# 06_SAMA7G54-DDR3.net
KiCad netlist of a schematic drawn in Altium Designer
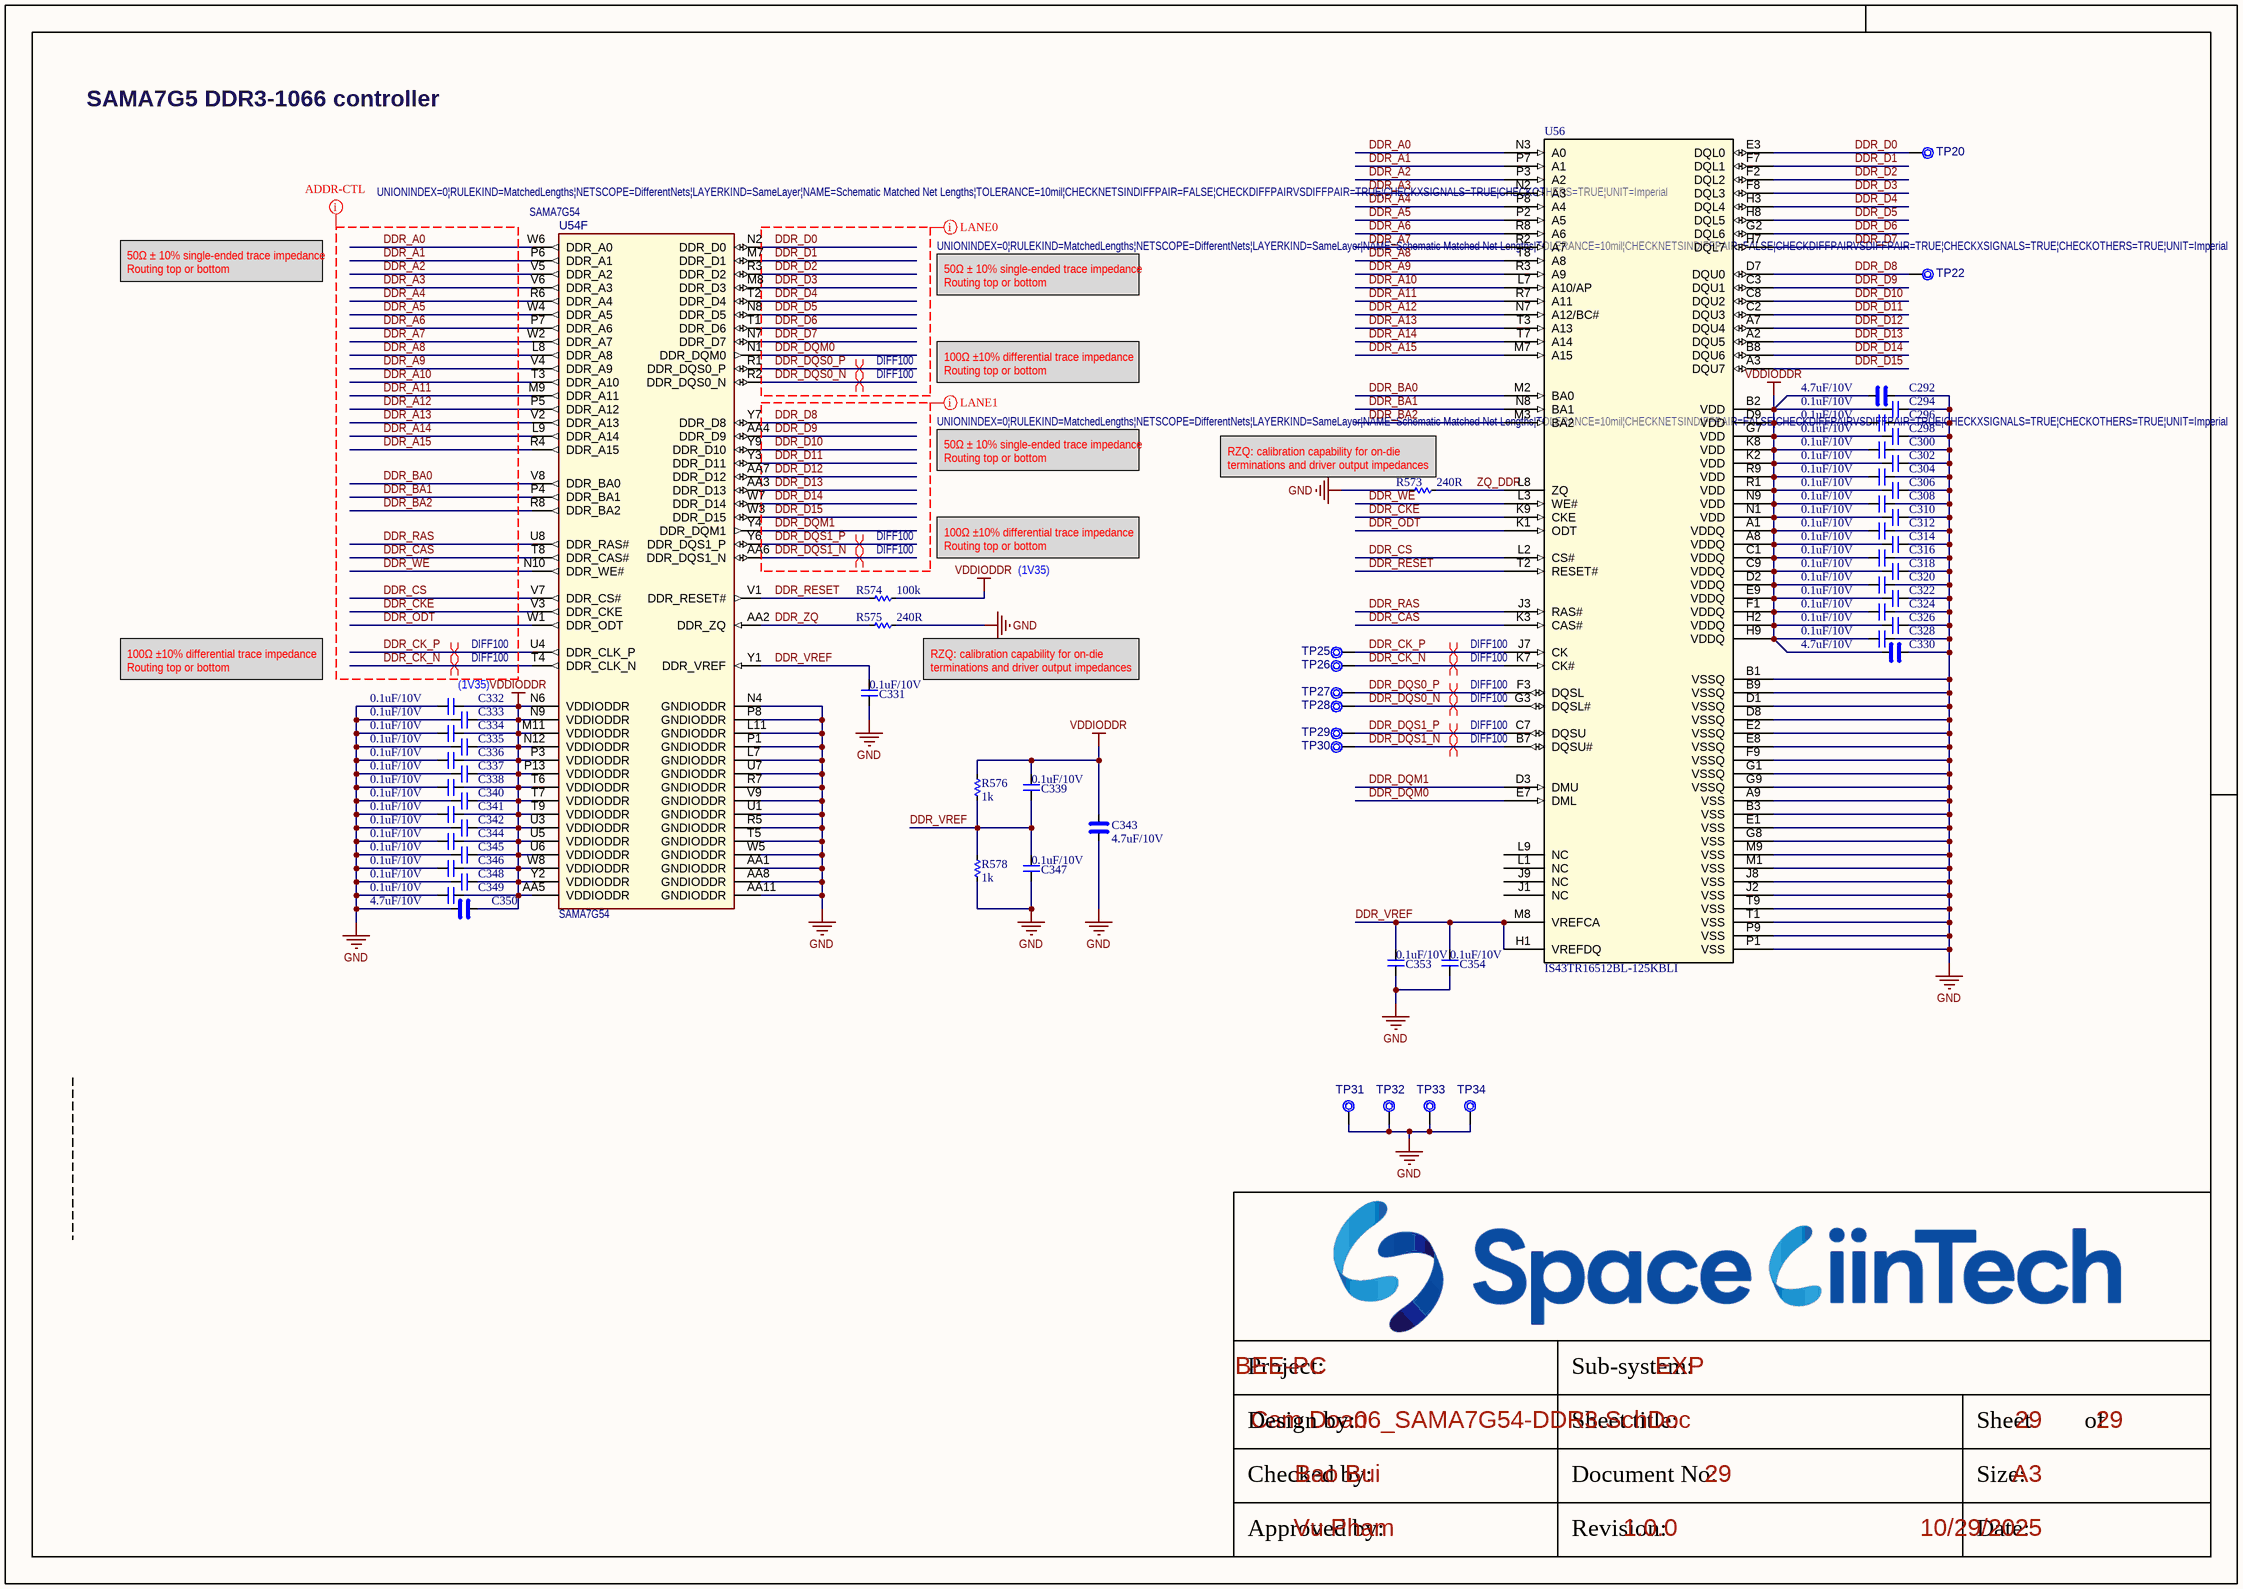
[diagram p0: 06_SAMA7G54-DDR3.SchDoc]

(export (version "E")
  (design (tool "Eeschema 10.0.6"))
  (components
    (comp (ref "C292")
      (value "4.7uF/10V")
      (footprint "CAP_C_1005X50_L")
      (description "CAP CHIP High Value")
      (libsource (lib "LABLIB") (part "_CAP_C_High_2"))
    )
    (comp (ref "C294")
      (value "0.1uF/10V")
      (footprint "CAP_C_0603x30")
      (description "CAP CHIP")
      (libsource (lib "LABLIB") (part "_CAP_C_2"))
    )
    (comp (ref "C296")
      (value "0.1uF/10V")
      (footprint "CAP_C_0603x30")
      (description "CAP CHIP")
      (libsource (lib "LABLIB") (part "_CAP_C_2"))
    )
    (comp (ref "C298")
      (value "0.1uF/10V")
      (footprint "CAP_C_0603x30")
      (description "CAP CHIP")
      (libsource (lib "LABLIB") (part "_CAP_C_2"))
    )
    (comp (ref "C300")
      (value "0.1uF/10V")
      (footprint "CAP_C_0603x30")
      (description "CAP CHIP")
      (libsource (lib "LABLIB") (part "_CAP_C_2"))
    )
    (comp (ref "C302")
      (value "0.1uF/10V")
      (footprint "CAP_C_0603x30")
      (description "CAP CHIP")
      (libsource (lib "LABLIB") (part "_CAP_C_2"))
    )
    (comp (ref "C304")
      (value "0.1uF/10V")
      (footprint "CAP_C_0603x30")
      (description "CAP CHIP")
      (libsource (lib "LABLIB") (part "_CAP_C_2"))
    )
    (comp (ref "C306")
      (value "0.1uF/10V")
      (footprint "CAP_C_0603x30")
      (description "CAP CHIP")
      (libsource (lib "LABLIB") (part "_CAP_C_2"))
    )
    (comp (ref "C308")
      (value "0.1uF/10V")
      (footprint "CAP_C_0603x30")
      (description "CAP CHIP")
      (libsource (lib "LABLIB") (part "_CAP_C_2"))
    )
    (comp (ref "C310")
      (value "0.1uF/10V")
      (footprint "CAP_C_0603x30")
      (description "CAP CHIP")
      (libsource (lib "LABLIB") (part "_CAP_C_2"))
    )
    (comp (ref "C312")
      (value "0.1uF/10V")
      (footprint "CAP_C_0603x30")
      (description "CAP CHIP")
      (libsource (lib "LABLIB") (part "_CAP_C_2"))
    )
    (comp (ref "C314")
      (value "0.1uF/10V")
      (footprint "CAP_C_0603x30")
      (description "CAP CHIP")
      (libsource (lib "LABLIB") (part "_CAP_C_2"))
    )
    (comp (ref "C316")
      (value "0.1uF/10V")
      (footprint "CAP_C_0603x30")
      (description "CAP CHIP")
      (libsource (lib "LABLIB") (part "_CAP_C_2"))
    )
    (comp (ref "C318")
      (value "0.1uF/10V")
      (footprint "CAP_C_0603x30")
      (description "CAP CHIP")
      (libsource (lib "LABLIB") (part "_CAP_C_2"))
    )
    (comp (ref "C320")
      (value "0.1uF/10V")
      (footprint "CAP_C_0603x30")
      (description "CAP CHIP")
      (libsource (lib "LABLIB") (part "_CAP_C_2"))
    )
    (comp (ref "C322")
      (value "0.1uF/10V")
      (footprint "CAP_C_0603x30")
      (description "CAP CHIP")
      (libsource (lib "LABLIB") (part "_CAP_C_2"))
    )
    (comp (ref "C324")
      (value "0.1uF/10V")
      (footprint "CAP_C_0603x30")
      (description "CAP CHIP")
      (libsource (lib "LABLIB") (part "_CAP_C_2"))
    )
    (comp (ref "C326")
      (value "0.1uF/10V")
      (footprint "CAP_C_0603x30")
      (description "CAP CHIP")
      (libsource (lib "LABLIB") (part "_CAP_C_2"))
    )
    (comp (ref "C328")
      (value "0.1uF/10V")
      (footprint "CAP_C_0603x30")
      (description "CAP CHIP")
      (libsource (lib "LABLIB") (part "_CAP_C_2"))
    )
    (comp (ref "C330")
      (value "4.7uF/10V")
      (footprint "CAP_C_1005X50_L")
      (description "CAP CHIP High Value")
      (libsource (lib "LABLIB") (part "_CAP_C_High_2"))
    )
    (comp (ref "C331")
      (value "0.1uF/10V")
      (footprint "CAP_C_0603x30")
      (description "CAP CHIP")
      (libsource (lib "LABLIB") (part "_CAP_C_2"))
    )
    (comp (ref "C332")
      (value "0.1uF/10V")
      (footprint "CAP_C_0603x30")
      (description "CAP CHIP")
      (libsource (lib "LABLIB") (part "_CAP_C_2"))
    )
    (comp (ref "C333")
      (value "0.1uF/10V")
      (footprint "CAP_C_0603x30")
      (description "CAP CHIP")
      (libsource (lib "LABLIB") (part "_CAP_C_2"))
    )
    (comp (ref "C334")
      (value "0.1uF/10V")
      (footprint "CAP_C_0603x30")
      (description "CAP CHIP")
      (libsource (lib "LABLIB") (part "_CAP_C_2"))
    )
    (comp (ref "C335")
      (value "0.1uF/10V")
      (footprint "CAP_C_0603x30")
      (description "CAP CHIP")
      (libsource (lib "LABLIB") (part "_CAP_C_2"))
    )
    (comp (ref "C336")
      (value "0.1uF/10V")
      (footprint "CAP_C_0603x30")
      (description "CAP CHIP")
      (libsource (lib "LABLIB") (part "_CAP_C_2"))
    )
    (comp (ref "C337")
      (value "0.1uF/10V")
      (footprint "CAP_C_0603x30")
      (description "CAP CHIP")
      (libsource (lib "LABLIB") (part "_CAP_C_2"))
    )
    (comp (ref "C338")
      (value "0.1uF/10V")
      (footprint "CAP_C_0603x30")
      (description "CAP CHIP")
      (libsource (lib "LABLIB") (part "_CAP_C_2"))
    )
    (comp (ref "C339")
      (value "0.1uF/10V")
      (footprint "CAP_C_0603x30")
      (description "CAP CHIP")
      (libsource (lib "LABLIB") (part "_CAP_C_2"))
    )
    (comp (ref "C340")
      (value "0.1uF/10V")
      (footprint "CAP_C_0603x30")
      (description "CAP CHIP")
      (libsource (lib "LABLIB") (part "_CAP_C_2"))
    )
    (comp (ref "C341")
      (value "0.1uF/10V")
      (footprint "CAP_C_0603x30")
      (description "CAP CHIP")
      (libsource (lib "LABLIB") (part "_CAP_C_2"))
    )
    (comp (ref "C342")
      (value "0.1uF/10V")
      (footprint "CAP_C_0603x30")
      (description "CAP CHIP")
      (libsource (lib "LABLIB") (part "_CAP_C_2"))
    )
    (comp (ref "C343")
      (value "4.7uF/10V")
      (footprint "CAP_C_1005X60")
      (description "CAP CHIP High Value")
      (libsource (lib "LABLIB") (part "_CAP_C_High_2"))
    )
    (comp (ref "C344")
      (value "0.1uF/10V")
      (footprint "CAP_C_0603x30")
      (description "CAP CHIP")
      (libsource (lib "LABLIB") (part "_CAP_C_2"))
    )
    (comp (ref "C345")
      (value "0.1uF/10V")
      (footprint "CAP_C_0603x30")
      (description "CAP CHIP")
      (libsource (lib "LABLIB") (part "_CAP_C_2"))
    )
    (comp (ref "C346")
      (value "0.1uF/10V")
      (footprint "CAP_C_0603x30")
      (description "CAP CHIP")
      (libsource (lib "LABLIB") (part "_CAP_C_2"))
    )
    (comp (ref "C347")
      (value "0.1uF/10V")
      (footprint "CAP_C_0603x30")
      (description "CAP CHIP")
      (libsource (lib "LABLIB") (part "_CAP_C_2"))
    )
    (comp (ref "C348")
      (value "0.1uF/10V")
      (footprint "CAP_C_0603x30")
      (description "CAP CHIP")
      (libsource (lib "LABLIB") (part "_CAP_C_2"))
    )
    (comp (ref "C349")
      (value "0.1uF/10V")
      (footprint "CAP_C_0603x30")
      (description "CAP CHIP")
      (libsource (lib "LABLIB") (part "_CAP_C_2"))
    )
    (comp (ref "C350")
      (value "4.7uF/10V")
      (footprint "CAP_C_1005X50_L")
      (description "CAP CHIP High Value")
      (libsource (lib "LABLIB") (part "_CAP_C_High_2"))
    )
    (comp (ref "C353")
      (value "0.1uF/10V")
      (footprint "CAP_C_0603x30")
      (description "CAP CHIP")
      (libsource (lib "LABLIB") (part "_CAP_C_2"))
    )
    (comp (ref "C354")
      (value "0.1uF/10V")
      (footprint "CAP_C_0603x30")
      (description "CAP CHIP")
      (libsource (lib "LABLIB") (part "_CAP_C_2"))
    )
    (comp (ref "R573")
      (value "240R")
      (footprint "RES_C_0603X30")
      (description "RES")
      (libsource (lib "LABLIB") (part "_RES_B_2"))
    )
    (comp (ref "R574")
      (value "100k")
      (footprint "RES_C_0603X30")
      (description "RES")
      (libsource (lib "LABLIB") (part "_RES_B_2"))
    )
    (comp (ref "R575")
      (value "240R")
      (footprint "RES_C_0603X30")
      (description "RES")
      (libsource (lib "LABLIB") (part "_RES_B_2"))
    )
    (comp (ref "R576")
      (value "1k")
      (footprint "RES_C_0603X30")
      (description "RES")
      (libsource (lib "LABLIB") (part "_RES_B_2"))
    )
    (comp (ref "R578")
      (value "1k")
      (footprint "RES_C_0603X30")
      (description "RES")
      (libsource (lib "LABLIB") (part "_RES_B_2"))
    )
    (comp (ref "TP20")
      (value "Test Point No BOM")
      (footprint "Testpoint_80")
      (description "Test Point")
      (fields (field (name "OWNER") "Cristian Papuc"))
      (libsource (lib "MCHP-CDB") (part "Test Point No BOM"))
    )
    (comp (ref "TP22")
      (value "Test Point No BOM")
      (footprint "Testpoint_80")
      (description "Test Point")
      (fields (field (name "OWNER") "Cristian Papuc"))
      (libsource (lib "MCHP-CDB") (part "Test Point No BOM"))
    )
    (comp (ref "TP25")
      (value "Test Point No BOM")
      (footprint "Testpoint_80")
      (description "Test Point")
      (fields (field (name "OWNER") "Cristian Papuc"))
      (libsource (lib "MCHP-CDB") (part "Test Point No BOM"))
    )
    (comp (ref "TP26")
      (value "Test Point No BOM")
      (footprint "Testpoint_80")
      (description "Test Point")
      (fields (field (name "OWNER") "Cristian Papuc"))
      (libsource (lib "MCHP-CDB") (part "Test Point No BOM"))
    )
    (comp (ref "TP27")
      (value "Test Point No BOM")
      (footprint "Testpoint_80")
      (description "Test Point")
      (fields (field (name "OWNER") "Cristian Papuc"))
      (libsource (lib "MCHP-CDB") (part "Test Point No BOM"))
    )
    (comp (ref "TP28")
      (value "Test Point No BOM")
      (footprint "Testpoint_80")
      (description "Test Point")
      (fields (field (name "OWNER") "Cristian Papuc"))
      (libsource (lib "MCHP-CDB") (part "Test Point No BOM"))
    )
    (comp (ref "TP29")
      (value "Test Point No BOM")
      (footprint "Testpoint_80")
      (description "Test Point")
      (fields (field (name "OWNER") "Cristian Papuc"))
      (libsource (lib "MCHP-CDB") (part "Test Point No BOM"))
    )
    (comp (ref "TP30")
      (value "Test Point No BOM")
      (footprint "Testpoint_80")
      (description "Test Point")
      (fields (field (name "OWNER") "Cristian Papuc"))
      (libsource (lib "MCHP-CDB") (part "Test Point No BOM"))
    )
    (comp (ref "TP31")
      (value "Test Point No BOM")
      (footprint "Testpoint_80")
      (description "Test Point")
      (fields (field (name "OWNER") "Cristian Papuc"))
      (libsource (lib "MCHP-CDB") (part "Test Point No BOM"))
    )
    (comp (ref "TP32")
      (value "Test Point No BOM")
      (footprint "Testpoint_80")
      (description "Test Point")
      (fields (field (name "OWNER") "Cristian Papuc"))
      (libsource (lib "MCHP-CDB") (part "Test Point No BOM"))
    )
    (comp (ref "TP33")
      (value "Test Point No BOM")
      (footprint "Testpoint_80")
      (description "Test Point")
      (fields (field (name "OWNER") "Cristian Papuc"))
      (libsource (lib "MCHP-CDB") (part "Test Point No BOM"))
    )
    (comp (ref "TP34")
      (value "Test Point No BOM")
      (footprint "Testpoint_80")
      (description "Test Point")
      (fields (field (name "OWNER") "Cristian Papuc"))
      (libsource (lib "MCHP-CDB") (part "Test Point No BOM"))
    )
    (comp (ref "U54")
      (value "SAMA7G54")
      (footprint "TFBGA-343_14x14")
      (description "SAMA7G54 MPU 1000MHz Cortex-A7 TFBGA-343")
      (fields (field (name "ALTIUM_VALUE") "SAMA7G54") (field (name "OWNER") "Ciprian Abramov"))
      (libsource (lib "MCHP-CDB") (part "SAMA7G54 TFBGA-343"))
    )
    (comp (ref "U56")
      (value "IS43TR16512BL-125KBLI")
      (footprint "TWBGA96_ISI")
      (description "DDR3L")
      (fields (field (name "COPYRIGHT") "Copyright (C) 2025 Ultra Librarian. All rights reserved."))
      (libsource (lib "LABLIB") (part "IC_RAM_IS43TR16512BL-125KBLI"))
    )
  )
  (nets
    (net (code "1") (name "/DDR_A0") (class "Default")
      (node (ref "U54") (pin "W6") (pinfunction "DDR_A0_W6") (pintype "output"))
      (node (ref "U56") (pin "N3") (pinfunction "A0_N3") (pintype "input"))
    )
    (net (code "2") (name "/DDR_A1") (class "Default")
      (node (ref "U54") (pin "P6") (pinfunction "DDR_A1_P6") (pintype "output"))
      (node (ref "U56") (pin "P7") (pinfunction "A1_P7") (pintype "input"))
    )
    (net (code "3") (name "/DDR_A2") (class "Default")
      (node (ref "U54") (pin "V5") (pinfunction "DDR_A2_V5") (pintype "output"))
      (node (ref "U56") (pin "P3") (pinfunction "A2_P3") (pintype "input"))
    )
    (net (code "4") (name "/DDR_A3") (class "Default")
      (node (ref "U54") (pin "V6") (pinfunction "DDR_A3_V6") (pintype "output"))
      (node (ref "U56") (pin "N2") (pinfunction "A3_N2") (pintype "input"))
    )
    (net (code "5") (name "/DDR_A4") (class "Default")
      (node (ref "U54") (pin "R6") (pinfunction "DDR_A4_R6") (pintype "output"))
      (node (ref "U56") (pin "P8") (pinfunction "A4_P8") (pintype "input"))
    )
    (net (code "6") (name "/DDR_A5") (class "Default")
      (node (ref "U54") (pin "W4") (pinfunction "DDR_A5_W4") (pintype "output"))
      (node (ref "U56") (pin "P2") (pinfunction "A5_P2") (pintype "input"))
    )
    (net (code "7") (name "/DDR_A6") (class "Default")
      (node (ref "U54") (pin "P7") (pinfunction "DDR_A6_P7") (pintype "output"))
      (node (ref "U56") (pin "R8") (pinfunction "A6_R8") (pintype "input"))
    )
    (net (code "8") (name "/DDR_A7") (class "Default")
      (node (ref "U54") (pin "W2") (pinfunction "DDR_A7_W2") (pintype "output"))
      (node (ref "U56") (pin "R2") (pinfunction "A7_R2") (pintype "input"))
    )
    (net (code "9") (name "/DDR_A8") (class "Default")
      (node (ref "U54") (pin "L8") (pinfunction "DDR_A8_L8") (pintype "output"))
      (node (ref "U56") (pin "T8") (pinfunction "A8_T8") (pintype "input"))
    )
    (net (code "10") (name "/DDR_A9") (class "Default")
      (node (ref "U54") (pin "V4") (pinfunction "DDR_A9_V4") (pintype "output"))
      (node (ref "U56") (pin "R3") (pinfunction "A9_R3") (pintype "input"))
    )
    (net (code "11") (name "/DDR_A10") (class "Default")
      (node (ref "U54") (pin "T3") (pinfunction "DDR_A10_T3") (pintype "output"))
      (node (ref "U56") (pin "L7") (pinfunction "A10/AP_L7") (pintype "input"))
    )
    (net (code "12") (name "/DDR_A11") (class "Default")
      (node (ref "U54") (pin "M9") (pinfunction "DDR_A11_M9") (pintype "output"))
      (node (ref "U56") (pin "R7") (pinfunction "A11_R7") (pintype "input"))
    )
    (net (code "13") (name "/DDR_A12") (class "Default")
      (node (ref "U54") (pin "P5") (pinfunction "DDR_A12_P5") (pintype "output"))
      (node (ref "U56") (pin "N7") (pinfunction "A12/BC#_N7") (pintype "input"))
    )
    (net (code "14") (name "/DDR_A13") (class "Default")
      (node (ref "U54") (pin "V2") (pinfunction "DDR_A13_V2") (pintype "output"))
      (node (ref "U56") (pin "T3") (pinfunction "A13_T3") (pintype "input"))
    )
    (net (code "15") (name "/DDR_A14") (class "Default")
      (node (ref "U54") (pin "L9") (pinfunction "DDR_A14_L9") (pintype "output"))
      (node (ref "U56") (pin "T7") (pinfunction "A14_T7") (pintype "input"))
    )
    (net (code "16") (name "/DDR_A15") (class "Default")
      (node (ref "U54") (pin "R4") (pinfunction "DDR_A15_R4") (pintype "output"))
      (node (ref "U56") (pin "M7") (pinfunction "A15_M7") (pintype "input"))
    )
    (net (code "17") (name "/DDR_BA0") (class "Default")
      (node (ref "U54") (pin "V8") (pinfunction "DDR_BA0_V8") (pintype "output"))
      (node (ref "U56") (pin "M2") (pinfunction "BA0_M2") (pintype "input"))
    )
    (net (code "18") (name "/DDR_BA1") (class "Default")
      (node (ref "U54") (pin "P4") (pinfunction "DDR_BA1_P4") (pintype "output"))
      (node (ref "U56") (pin "N8") (pinfunction "BA1_N8") (pintype "input"))
    )
    (net (code "19") (name "/DDR_BA2") (class "Default")
      (node (ref "U54") (pin "R8") (pinfunction "DDR_BA2_R8") (pintype "output"))
      (node (ref "U56") (pin "M3") (pinfunction "BA2_M3") (pintype "input"))
    )
    (net (code "20") (name "/DDR_CAS") (class "Default")
      (node (ref "U54") (pin "T8") (pinfunction "DDR_CAS#_T8") (pintype "output"))
      (node (ref "U56") (pin "K3") (pinfunction "CAS#_K3") (pintype "input"))
    )
    (net (code "21") (name "/DDR_CKE") (class "Default")
      (node (ref "U54") (pin "V3") (pinfunction "DDR_CKE_V3") (pintype "output"))
      (node (ref "U56") (pin "K9") (pinfunction "CKE_K9") (pintype "input"))
    )
    (net (code "22") (name "/DDR_CK_N") (class "Default")
      (node (ref "TP26") (pin "1") (pinfunction "1_1") (pintype "passive"))
      (node (ref "U54") (pin "T4") (pinfunction "DDR_CLK_N_T4") (pintype "output"))
      (node (ref "U56") (pin "K7") (pinfunction "CK#_K7") (pintype "input"))
    )
    (net (code "23") (name "/DDR_CK_P") (class "Default")
      (node (ref "TP25") (pin "1") (pinfunction "1_1") (pintype "passive"))
      (node (ref "U54") (pin "U4") (pinfunction "DDR_CLK_P_U4") (pintype "output"))
      (node (ref "U56") (pin "J7") (pinfunction "CK_J7") (pintype "input"))
    )
    (net (code "24") (name "/DDR_CS") (class "Default")
      (node (ref "U54") (pin "V7") (pinfunction "DDR_CS#_V7") (pintype "output"))
      (node (ref "U56") (pin "L2") (pinfunction "CS#_L2") (pintype "input"))
    )
    (net (code "25") (name "/DDR_D0") (class "Default")
      (node (ref "TP20") (pin "1") (pinfunction "1_1") (pintype "passive"))
      (node (ref "U54") (pin "N2") (pinfunction "DDR_D0_N2") (pintype "bidirectional"))
      (node (ref "U56") (pin "E3") (pinfunction "DQL0_E3") (pintype "bidirectional"))
    )
    (net (code "26") (name "/DDR_D1") (class "Default")
      (node (ref "U54") (pin "M7") (pinfunction "DDR_D1_M7") (pintype "bidirectional"))
      (node (ref "U56") (pin "F7") (pinfunction "DQL1_F7") (pintype "bidirectional"))
    )
    (net (code "27") (name "/DDR_D2") (class "Default")
      (node (ref "U54") (pin "R3") (pinfunction "DDR_D2_R3") (pintype "bidirectional"))
      (node (ref "U56") (pin "F2") (pinfunction "DQL2_F2") (pintype "bidirectional"))
    )
    (net (code "28") (name "/DDR_D3") (class "Default")
      (node (ref "U54") (pin "M8") (pinfunction "DDR_D3_M8") (pintype "bidirectional"))
      (node (ref "U56") (pin "F8") (pinfunction "DQL3_F8") (pintype "bidirectional"))
    )
    (net (code "29") (name "/DDR_D4") (class "Default")
      (node (ref "U54") (pin "T2") (pinfunction "DDR_D4_T2") (pintype "bidirectional"))
      (node (ref "U56") (pin "H3") (pinfunction "DQL4_H3") (pintype "bidirectional"))
    )
    (net (code "30") (name "/DDR_D5") (class "Default")
      (node (ref "U54") (pin "N8") (pinfunction "DDR_D5_N8") (pintype "bidirectional"))
      (node (ref "U56") (pin "H8") (pinfunction "DQL5_H8") (pintype "bidirectional"))
    )
    (net (code "31") (name "/DDR_D6") (class "Default")
      (node (ref "U54") (pin "T1") (pinfunction "DDR_D6_T1") (pintype "bidirectional"))
      (node (ref "U56") (pin "G2") (pinfunction "DQL6_G2") (pintype "bidirectional"))
    )
    (net (code "32") (name "/DDR_D7") (class "Default")
      (node (ref "U54") (pin "N7") (pinfunction "DDR_D7_N7") (pintype "bidirectional"))
      (node (ref "U56") (pin "H7") (pinfunction "DQL7_H7") (pintype "bidirectional"))
    )
    (net (code "33") (name "/DDR_D8") (class "Default")
      (node (ref "TP22") (pin "1") (pinfunction "1_1") (pintype "passive"))
      (node (ref "U54") (pin "Y7") (pinfunction "DDR_D8_Y7") (pintype "bidirectional"))
      (node (ref "U56") (pin "D7") (pinfunction "DQU0_D7") (pintype "bidirectional"))
    )
    (net (code "34") (name "/DDR_D9") (class "Default")
      (node (ref "U54") (pin "AA4") (pinfunction "DDR_D9_AA4") (pintype "bidirectional"))
      (node (ref "U56") (pin "C3") (pinfunction "DQU1_C3") (pintype "bidirectional"))
    )
    (net (code "35") (name "/DDR_D10") (class "Default")
      (node (ref "U54") (pin "Y9") (pinfunction "DDR_D10_Y9") (pintype "bidirectional"))
      (node (ref "U56") (pin "C8") (pinfunction "DQU2_C8") (pintype "bidirectional"))
    )
    (net (code "36") (name "/DDR_D11") (class "Default")
      (node (ref "U54") (pin "Y3") (pinfunction "DDR_D11_Y3") (pintype "bidirectional"))
      (node (ref "U56") (pin "C2") (pinfunction "DQU3_C2") (pintype "bidirectional"))
    )
    (net (code "37") (name "/DDR_D12") (class "Default")
      (node (ref "U54") (pin "AA7") (pinfunction "DDR_D12_AA7") (pintype "bidirectional"))
      (node (ref "U56") (pin "A7") (pinfunction "DQU4_A7") (pintype "bidirectional"))
    )
    (net (code "38") (name "/DDR_D13") (class "Default")
      (node (ref "U54") (pin "AA3") (pinfunction "DDR_D13_AA3") (pintype "bidirectional"))
      (node (ref "U56") (pin "A2") (pinfunction "DQU5_A2") (pintype "bidirectional"))
    )
    (net (code "39") (name "/DDR_D14") (class "Default")
      (node (ref "U54") (pin "W7") (pinfunction "DDR_D14_W7") (pintype "bidirectional"))
      (node (ref "U56") (pin "B8") (pinfunction "DQU6_B8") (pintype "bidirectional"))
    )
    (net (code "40") (name "/DDR_D15") (class "Default")
      (node (ref "U54") (pin "W3") (pinfunction "DDR_D15_W3") (pintype "bidirectional"))
      (node (ref "U56") (pin "A3") (pinfunction "DQU7_A3") (pintype "bidirectional"))
    )
    (net (code "41") (name "/DDR_DQM0") (class "Default")
      (node (ref "U54") (pin "N1") (pinfunction "DDR_DQM0_N1") (pintype "output"))
      (node (ref "U56") (pin "E7") (pinfunction "DML_E7") (pintype "input"))
    )
    (net (code "42") (name "/DDR_DQM1") (class "Default")
      (node (ref "U54") (pin "Y4") (pinfunction "DDR_DQM1_Y4") (pintype "output"))
      (node (ref "U56") (pin "D3") (pinfunction "DMU_D3") (pintype "input"))
    )
    (net (code "43") (name "/DDR_DQS0_N") (class "Default")
      (node (ref "TP28") (pin "1") (pinfunction "1_1") (pintype "passive"))
      (node (ref "U54") (pin "R2") (pinfunction "DDR_DQS0_N_R2") (pintype "bidirectional"))
      (node (ref "U56") (pin "G3") (pinfunction "DQSL#_G3") (pintype "bidirectional"))
    )
    (net (code "44") (name "/DDR_DQS0_P") (class "Default")
      (node (ref "TP27") (pin "1") (pinfunction "1_1") (pintype "passive"))
      (node (ref "U54") (pin "R1") (pinfunction "DDR_DQS0_P_R1") (pintype "bidirectional"))
      (node (ref "U56") (pin "F3") (pinfunction "DQSL_F3") (pintype "bidirectional"))
    )
    (net (code "45") (name "/DDR_DQS1_N") (class "Default")
      (node (ref "TP30") (pin "1") (pinfunction "1_1") (pintype "passive"))
      (node (ref "U54") (pin "AA6") (pinfunction "DDR_DQS1_N_AA6") (pintype "bidirectional"))
      (node (ref "U56") (pin "B7") (pinfunction "DQSU#_B7") (pintype "bidirectional"))
    )
    (net (code "46") (name "/DDR_DQS1_P") (class "Default")
      (node (ref "TP29") (pin "1") (pinfunction "1_1") (pintype "passive"))
      (node (ref "U54") (pin "Y6") (pinfunction "DDR_DQS1_P_Y6") (pintype "bidirectional"))
      (node (ref "U56") (pin "C7") (pinfunction "DQSU_C7") (pintype "bidirectional"))
    )
    (net (code "47") (name "/DDR_ODT") (class "Default")
      (node (ref "U54") (pin "W1") (pinfunction "DDR_ODT_W1") (pintype "output"))
      (node (ref "U56") (pin "K1") (pinfunction "ODT_K1") (pintype "input"))
    )
    (net (code "48") (name "/DDR_RAS") (class "Default")
      (node (ref "U54") (pin "U8") (pinfunction "DDR_RAS#_U8") (pintype "output"))
      (node (ref "U56") (pin "J3") (pinfunction "RAS#_J3") (pintype "input"))
    )
    (net (code "49") (name "/DDR_RESET") (class "Default")
      (node (ref "R574") (pin "2") (pinfunction "2_2") (pintype "passive"))
      (node (ref "U54") (pin "V1") (pinfunction "DDR_RESET#_V1") (pintype "output"))
      (node (ref "U56") (pin "T2") (pinfunction "RESET#_T2") (pintype "input"))
    )
    (net (code "50") (name "/DDR_VREF") (class "Default")
      (node (ref "C331") (pin "1") (pinfunction "1_1") (pintype "passive"))
      (node (ref "C339") (pin "2") (pinfunction "2_2") (pintype "passive"))
      (node (ref "C347") (pin "1") (pinfunction "1_1") (pintype "passive"))
      (node (ref "C353") (pin "1") (pinfunction "1_1") (pintype "passive"))
      (node (ref "C354") (pin "1") (pinfunction "1_1") (pintype "passive"))
      (node (ref "R576") (pin "2") (pinfunction "2_2") (pintype "passive"))
      (node (ref "R578") (pin "1") (pinfunction "1_1") (pintype "passive"))
      (node (ref "U54") (pin "Y1") (pinfunction "DDR_VREF_Y1") (pintype "input"))
      (node (ref "U56") (pin "H1") (pinfunction "VREFDQ_H1") (pintype "power_in"))
      (node (ref "U56") (pin "M8") (pinfunction "VREFCA_M8") (pintype "power_in"))
    )
    (net (code "51") (name "/DDR_WE") (class "Default")
      (node (ref "U54") (pin "N10") (pinfunction "DDR_WE#_N10") (pintype "output"))
      (node (ref "U56") (pin "L3") (pinfunction "WE#_L3") (pintype "input"))
    )
    (net (code "52") (name "/DDR_ZQ") (class "Default")
      (node (ref "R575") (pin "2") (pinfunction "2_2") (pintype "passive"))
      (node (ref "U54") (pin "AA2") (pinfunction "DDR_ZQ_AA2") (pintype "input"))
    )
    (net (code "53") (name "/ZQ_DDR") (class "Default")
      (node (ref "R573") (pin "1") (pinfunction "1_1") (pintype "passive"))
      (node (ref "U56") (pin "L8") (pinfunction "ZQ_L8") (pintype "power_in"))
    )
    (net (code "54") (name "GND") (class "Default")
      (node (ref "C292") (pin "1") (pinfunction "1_1") (pintype "passive"))
      (node (ref "C294") (pin "1") (pinfunction "1_1") (pintype "passive"))
      (node (ref "C296") (pin "1") (pinfunction "1_1") (pintype "passive"))
      (node (ref "C298") (pin "1") (pinfunction "1_1") (pintype "passive"))
      (node (ref "C300") (pin "1") (pinfunction "1_1") (pintype "passive"))
      (node (ref "C302") (pin "1") (pinfunction "1_1") (pintype "passive"))
      (node (ref "C304") (pin "1") (pinfunction "1_1") (pintype "passive"))
      (node (ref "C306") (pin "1") (pinfunction "1_1") (pintype "passive"))
      (node (ref "C308") (pin "1") (pinfunction "1_1") (pintype "passive"))
      (node (ref "C310") (pin "1") (pinfunction "1_1") (pintype "passive"))
      (node (ref "C312") (pin "1") (pinfunction "1_1") (pintype "passive"))
      (node (ref "C314") (pin "1") (pinfunction "1_1") (pintype "passive"))
      (node (ref "C316") (pin "1") (pinfunction "1_1") (pintype "passive"))
      (node (ref "C318") (pin "1") (pinfunction "1_1") (pintype "passive"))
      (node (ref "C320") (pin "1") (pinfunction "1_1") (pintype "passive"))
      (node (ref "C322") (pin "1") (pinfunction "1_1") (pintype "passive"))
      (node (ref "C324") (pin "1") (pinfunction "1_1") (pintype "passive"))
      (node (ref "C326") (pin "1") (pinfunction "1_1") (pintype "passive"))
      (node (ref "C328") (pin "1") (pinfunction "1_1") (pintype "passive"))
      (node (ref "C330") (pin "1") (pinfunction "1_1") (pintype "passive"))
      (node (ref "C331") (pin "2") (pinfunction "2_2") (pintype "passive"))
      (node (ref "C332") (pin "2") (pinfunction "2_2") (pintype "passive"))
      (node (ref "C333") (pin "2") (pinfunction "2_2") (pintype "passive"))
      (node (ref "C334") (pin "2") (pinfunction "2_2") (pintype "passive"))
      (node (ref "C335") (pin "2") (pinfunction "2_2") (pintype "passive"))
      (node (ref "C336") (pin "2") (pinfunction "2_2") (pintype "passive"))
      (node (ref "C337") (pin "2") (pinfunction "2_2") (pintype "passive"))
      (node (ref "C338") (pin "2") (pinfunction "2_2") (pintype "passive"))
      (node (ref "C340") (pin "2") (pinfunction "2_2") (pintype "passive"))
      (node (ref "C341") (pin "2") (pinfunction "2_2") (pintype "passive"))
      (node (ref "C342") (pin "2") (pinfunction "2_2") (pintype "passive"))
      (node (ref "C343") (pin "2") (pinfunction "2_2") (pintype "passive"))
      (node (ref "C344") (pin "2") (pinfunction "2_2") (pintype "passive"))
      (node (ref "C345") (pin "2") (pinfunction "2_2") (pintype "passive"))
      (node (ref "C346") (pin "2") (pinfunction "2_2") (pintype "passive"))
      (node (ref "C347") (pin "2") (pinfunction "2_2") (pintype "passive"))
      (node (ref "C348") (pin "2") (pinfunction "2_2") (pintype "passive"))
      (node (ref "C349") (pin "2") (pinfunction "2_2") (pintype "passive"))
      (node (ref "C350") (pin "2") (pinfunction "2_2") (pintype "passive"))
      (node (ref "C353") (pin "2") (pinfunction "2_2") (pintype "passive"))
      (node (ref "C354") (pin "2") (pinfunction "2_2") (pintype "passive"))
      (node (ref "R573") (pin "2") (pinfunction "2_2") (pintype "passive"))
      (node (ref "R575") (pin "1") (pinfunction "1_1") (pintype "passive"))
      (node (ref "R578") (pin "2") (pinfunction "2_2") (pintype "passive"))
      (node (ref "TP31") (pin "1") (pinfunction "1_1") (pintype "passive"))
      (node (ref "TP32") (pin "1") (pinfunction "1_1") (pintype "passive"))
      (node (ref "TP33") (pin "1") (pinfunction "1_1") (pintype "passive"))
      (node (ref "TP34") (pin "1") (pinfunction "1_1") (pintype "passive"))
      (node (ref "U54") (pin "AA1") (pinfunction "GNDIODDR_AA1") (pintype "power_in"))
      (node (ref "U54") (pin "AA11") (pinfunction "GNDIODDR_AA11") (pintype "power_in"))
      (node (ref "U54") (pin "AA8") (pinfunction "GNDIODDR_AA8") (pintype "power_in"))
      (node (ref "U54") (pin "L11") (pinfunction "GNDIODDR_L11") (pintype "power_in"))
      (node (ref "U54") (pin "L7") (pinfunction "GNDIODDR_L7") (pintype "power_in"))
      (node (ref "U54") (pin "N4") (pinfunction "GNDIODDR_N4") (pintype "power_in"))
      (node (ref "U54") (pin "P1") (pinfunction "GNDIODDR_P1") (pintype "power_in"))
      (node (ref "U54") (pin "P8") (pinfunction "GNDIODDR_P8") (pintype "power_in"))
      (node (ref "U54") (pin "R5") (pinfunction "GNDIODDR_R5") (pintype "power_in"))
      (node (ref "U54") (pin "R7") (pinfunction "GNDIODDR_R7") (pintype "power_in"))
      (node (ref "U54") (pin "T5") (pinfunction "GNDIODDR_T5") (pintype "power_in"))
      (node (ref "U54") (pin "U1") (pinfunction "GNDIODDR_U1") (pintype "power_in"))
      (node (ref "U54") (pin "U7") (pinfunction "GNDIODDR_U7") (pintype "power_in"))
      (node (ref "U54") (pin "V9") (pinfunction "GNDIODDR_V9") (pintype "power_in"))
      (node (ref "U54") (pin "W5") (pinfunction "GNDIODDR_W5") (pintype "power_in"))
      (node (ref "U56") (pin "A9") (pinfunction "VSS_A9") (pintype "power_in"))
      (node (ref "U56") (pin "B1") (pinfunction "VSSQ_B1") (pintype "power_in"))
      (node (ref "U56") (pin "B3") (pinfunction "VSS_B3") (pintype "power_in"))
      (node (ref "U56") (pin "B9") (pinfunction "VSSQ_B9") (pintype "power_in"))
      (node (ref "U56") (pin "D1") (pinfunction "VSSQ_D1") (pintype "power_in"))
      (node (ref "U56") (pin "D8") (pinfunction "VSSQ_D8") (pintype "power_in"))
      (node (ref "U56") (pin "E1") (pinfunction "VSS_E1") (pintype "power_in"))
      (node (ref "U56") (pin "E2") (pinfunction "VSSQ_E2") (pintype "power_in"))
      (node (ref "U56") (pin "E8") (pinfunction "VSSQ_E8") (pintype "power_in"))
      (node (ref "U56") (pin "F9") (pinfunction "VSSQ_F9") (pintype "power_in"))
      (node (ref "U56") (pin "G1") (pinfunction "VSSQ_G1") (pintype "power_in"))
      (node (ref "U56") (pin "G8") (pinfunction "VSS_G8") (pintype "power_in"))
      (node (ref "U56") (pin "G9") (pinfunction "VSSQ_G9") (pintype "power_in"))
      (node (ref "U56") (pin "J2") (pinfunction "VSS_J2") (pintype "power_in"))
      (node (ref "U56") (pin "J8") (pinfunction "VSS_J8") (pintype "power_in"))
      (node (ref "U56") (pin "M1") (pinfunction "VSS_M1") (pintype "power_in"))
      (node (ref "U56") (pin "M9") (pinfunction "VSS_M9") (pintype "power_in"))
      (node (ref "U56") (pin "P1") (pinfunction "VSS_P1") (pintype "power_in"))
      (node (ref "U56") (pin "P9") (pinfunction "VSS_P9") (pintype "power_in"))
      (node (ref "U56") (pin "T1") (pinfunction "VSS_T1") (pintype "power_in"))
      (node (ref "U56") (pin "T9") (pinfunction "VSS_T9") (pintype "power_in"))
    )
    (net (code "55") (name "VDDIODDR") (class "Default")
      (node (ref "C292") (pin "2") (pinfunction "2_2") (pintype "passive"))
      (node (ref "C294") (pin "2") (pinfunction "2_2") (pintype "passive"))
      (node (ref "C296") (pin "2") (pinfunction "2_2") (pintype "passive"))
      (node (ref "C298") (pin "2") (pinfunction "2_2") (pintype "passive"))
      (node (ref "C300") (pin "2") (pinfunction "2_2") (pintype "passive"))
      (node (ref "C302") (pin "2") (pinfunction "2_2") (pintype "passive"))
      (node (ref "C304") (pin "2") (pinfunction "2_2") (pintype "passive"))
      (node (ref "C306") (pin "2") (pinfunction "2_2") (pintype "passive"))
      (node (ref "C308") (pin "2") (pinfunction "2_2") (pintype "passive"))
      (node (ref "C310") (pin "2") (pinfunction "2_2") (pintype "passive"))
      (node (ref "C312") (pin "2") (pinfunction "2_2") (pintype "passive"))
      (node (ref "C314") (pin "2") (pinfunction "2_2") (pintype "passive"))
      (node (ref "C316") (pin "2") (pinfunction "2_2") (pintype "passive"))
      (node (ref "C318") (pin "2") (pinfunction "2_2") (pintype "passive"))
      (node (ref "C320") (pin "2") (pinfunction "2_2") (pintype "passive"))
      (node (ref "C322") (pin "2") (pinfunction "2_2") (pintype "passive"))
      (node (ref "C324") (pin "2") (pinfunction "2_2") (pintype "passive"))
      (node (ref "C326") (pin "2") (pinfunction "2_2") (pintype "passive"))
      (node (ref "C328") (pin "2") (pinfunction "2_2") (pintype "passive"))
      (node (ref "C330") (pin "2") (pinfunction "2_2") (pintype "passive"))
      (node (ref "C332") (pin "1") (pinfunction "1_1") (pintype "passive"))
      (node (ref "C333") (pin "1") (pinfunction "1_1") (pintype "passive"))
      (node (ref "C334") (pin "1") (pinfunction "1_1") (pintype "passive"))
      (node (ref "C335") (pin "1") (pinfunction "1_1") (pintype "passive"))
      (node (ref "C336") (pin "1") (pinfunction "1_1") (pintype "passive"))
      (node (ref "C337") (pin "1") (pinfunction "1_1") (pintype "passive"))
      (node (ref "C338") (pin "1") (pinfunction "1_1") (pintype "passive"))
      (node (ref "C339") (pin "1") (pinfunction "1_1") (pintype "passive"))
      (node (ref "C340") (pin "1") (pinfunction "1_1") (pintype "passive"))
      (node (ref "C341") (pin "1") (pinfunction "1_1") (pintype "passive"))
      (node (ref "C342") (pin "1") (pinfunction "1_1") (pintype "passive"))
      (node (ref "C343") (pin "1") (pinfunction "1_1") (pintype "passive"))
      (node (ref "C344") (pin "1") (pinfunction "1_1") (pintype "passive"))
      (node (ref "C345") (pin "1") (pinfunction "1_1") (pintype "passive"))
      (node (ref "C346") (pin "1") (pinfunction "1_1") (pintype "passive"))
      (node (ref "C348") (pin "1") (pinfunction "1_1") (pintype "passive"))
      (node (ref "C349") (pin "1") (pinfunction "1_1") (pintype "passive"))
      (node (ref "C350") (pin "1") (pinfunction "1_1") (pintype "passive"))
      (node (ref "R574") (pin "1") (pinfunction "1_1") (pintype "passive"))
      (node (ref "R576") (pin "1") (pinfunction "1_1") (pintype "passive"))
      (node (ref "U54") (pin "AA5") (pinfunction "VDDIODDR_AA5") (pintype "power_in"))
      (node (ref "U54") (pin "M11") (pinfunction "VDDIODDR_M11") (pintype "power_in"))
      (node (ref "U54") (pin "N12") (pinfunction "VDDIODDR_N12") (pintype "power_in"))
      (node (ref "U54") (pin "N6") (pinfunction "VDDIODDR_N6") (pintype "power_in"))
      (node (ref "U54") (pin "N9") (pinfunction "VDDIODDR_N9") (pintype "power_in"))
      (node (ref "U54") (pin "P13") (pinfunction "VDDIODDR_P13") (pintype "power_in"))
      (node (ref "U54") (pin "P3") (pinfunction "VDDIODDR_P3") (pintype "power_in"))
      (node (ref "U54") (pin "T6") (pinfunction "VDDIODDR_T6") (pintype "power_in"))
      (node (ref "U54") (pin "T7") (pinfunction "VDDIODDR_T7") (pintype "power_in"))
      (node (ref "U54") (pin "T9") (pinfunction "VDDIODDR_T9") (pintype "power_in"))
      (node (ref "U54") (pin "U3") (pinfunction "VDDIODDR_U3") (pintype "power_in"))
      (node (ref "U54") (pin "U5") (pinfunction "VDDIODDR_U5") (pintype "power_in"))
      (node (ref "U54") (pin "U6") (pinfunction "VDDIODDR_U6") (pintype "power_in"))
      (node (ref "U54") (pin "W8") (pinfunction "VDDIODDR_W8") (pintype "power_in"))
      (node (ref "U54") (pin "Y2") (pinfunction "VDDIODDR_Y2") (pintype "power_in"))
      (node (ref "U56") (pin "A1") (pinfunction "VDDQ_A1") (pintype "power_in"))
      (node (ref "U56") (pin "A8") (pinfunction "VDDQ_A8") (pintype "power_in"))
      (node (ref "U56") (pin "B2") (pinfunction "VDD_B2") (pintype "power_in"))
      (node (ref "U56") (pin "C1") (pinfunction "VDDQ_C1") (pintype "power_in"))
      (node (ref "U56") (pin "C9") (pinfunction "VDDQ_C9") (pintype "power_in"))
      (node (ref "U56") (pin "D2") (pinfunction "VDDQ_D2") (pintype "power_in"))
      (node (ref "U56") (pin "D9") (pinfunction "VDD_D9") (pintype "power_in"))
      (node (ref "U56") (pin "E9") (pinfunction "VDDQ_E9") (pintype "power_in"))
      (node (ref "U56") (pin "F1") (pinfunction "VDDQ_F1") (pintype "power_in"))
      (node (ref "U56") (pin "G7") (pinfunction "VDD_G7") (pintype "power_in"))
      (node (ref "U56") (pin "H2") (pinfunction "VDDQ_H2") (pintype "power_in"))
      (node (ref "U56") (pin "H9") (pinfunction "VDDQ_H9") (pintype "power_in"))
      (node (ref "U56") (pin "K2") (pinfunction "VDD_K2") (pintype "power_in"))
      (node (ref "U56") (pin "K8") (pinfunction "VDD_K8") (pintype "power_in"))
      (node (ref "U56") (pin "N1") (pinfunction "VDD_N1") (pintype "power_in"))
      (node (ref "U56") (pin "N9") (pinfunction "VDD_N9") (pintype "power_in"))
      (node (ref "U56") (pin "R1") (pinfunction "VDD_R1") (pintype "power_in"))
      (node (ref "U56") (pin "R9") (pinfunction "VDD_R9") (pintype "power_in"))
    )
    (net (code "56") (name "unconnected-(U56-NC-PadJ1)") (class "Default")
      (node (ref "U56") (pin "J1") (pinfunction "NC_J1") (pintype "passive"))
    )
    (net (code "57") (name "unconnected-(U56-NC-PadJ9)") (class "Default")
      (node (ref "U56") (pin "J9") (pinfunction "NC_J9") (pintype "passive"))
    )
    (net (code "58") (name "unconnected-(U56-NC-PadL1)") (class "Default")
      (node (ref "U56") (pin "L1") (pinfunction "NC_L1") (pintype "passive"))
    )
    (net (code "59") (name "unconnected-(U56-NC-PadL9)") (class "Default")
      (node (ref "U56") (pin "L9") (pinfunction "NC_L9") (pintype "passive"))
    )
  )
)
